# circuit.net
KiCad netlist of a schematic drawn in EAGLE
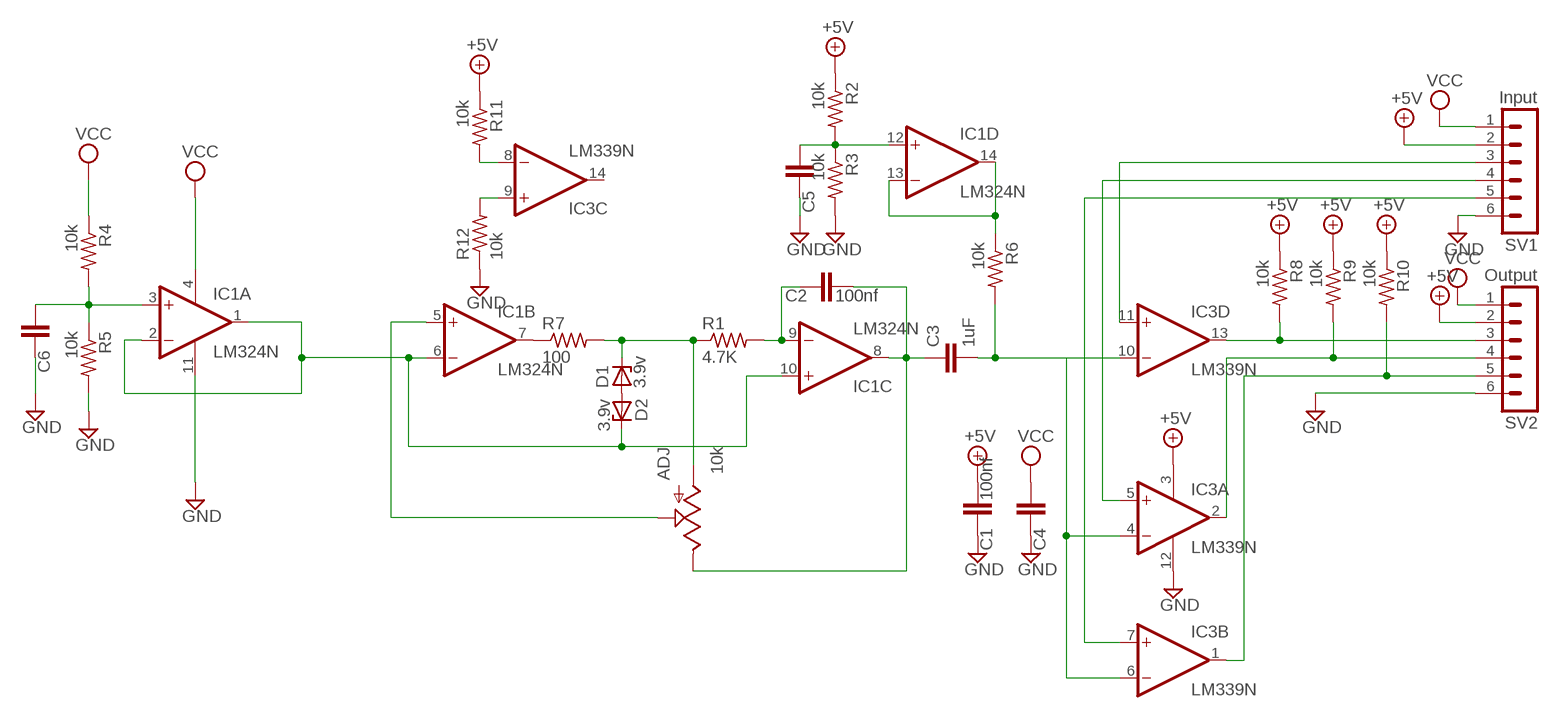
[diagram p0: schematic, sheet 1]

(export (version "E")
  (design (tool "Eeschema 10.0.6"))
  (components
    (comp (ref "ADJ")
      (value "10k")
      (footprint "eagle-import:TRIM_POT")
      (libsource (lib "eagle-import") (part "POTTRIM"))
    )
    (comp (ref "C1")
      (value "100nf")
      (footprint "eagle-import:C050-024X044")
      (libsource (lib "eagle-import") (part "C-EU050-024X044"))
    )
    (comp (ref "C2")
      (value "100nf")
      (footprint "eagle-import:C050-024X044")
      (libsource (lib "eagle-import") (part "C-EU050-024X044"))
    )
    (comp (ref "C3")
      (value "1uF")
      (footprint "eagle-import:C050-035X075")
      (libsource (lib "eagle-import") (part "resistor_C-EU050-035X075"))
    )
    (comp (ref "C4")
      (value "100nf")
      (footprint "eagle-import:C050-024X044")
      (libsource (lib "eagle-import") (part "C-EU050-024X044"))
    )
    (comp (ref "C5")
      (value "100nf")
      (footprint "eagle-import:C050-024X044")
      (libsource (lib "eagle-import") (part "C-EU050-024X044"))
    )
    (comp (ref "C6")
      (value "100nf")
      (footprint "eagle-import:C050-024X044")
      (libsource (lib "eagle-import") (part "C-EU050-024X044"))
    )
    (comp (ref "D1")
      (value "3.9v")
      (footprint "eagle-import:DO41Z10")
      (libsource (lib "eagle-import") (part "ZENER-DIODEDO41Z10"))
    )
    (comp (ref "D2")
      (value "3.9v")
      (footprint "eagle-import:DO41Z10")
      (libsource (lib "eagle-import") (part "ZENER-DIODEDO41Z10"))
    )
    (comp (ref "IC1")
      (value "LM324N")
      (footprint "eagle-import:DIL14")
      (libsource (lib "eagle-import") (part "LM324N"))
    )
    (comp (ref "IC3")
      (value "LM339N")
      (footprint "eagle-import:DIL14")
      (libsource (lib "eagle-import") (part "LM339N"))
    )
    (comp (ref "R1")
      (value "4.7K")
      (footprint "eagle-import:0207_12")
      (libsource (lib "eagle-import") (part "R-US_0207/12"))
    )
    (comp (ref "R2")
      (value "10k")
      (footprint "eagle-import:0207_10")
      (libsource (lib "eagle-import") (part "R-US_0207/10"))
    )
    (comp (ref "R3")
      (value "10k")
      (footprint "eagle-import:0207_10")
      (libsource (lib "eagle-import") (part "R-US_0207/10"))
    )
    (comp (ref "R4")
      (value "10k")
      (footprint "eagle-import:0207_10")
      (libsource (lib "eagle-import") (part "R-US_0207/10"))
    )
    (comp (ref "R5")
      (value "10k")
      (footprint "eagle-import:0207_10")
      (libsource (lib "eagle-import") (part "R-US_0207/10"))
    )
    (comp (ref "R6")
      (value "10k")
      (footprint "eagle-import:0207_10")
      (libsource (lib "eagle-import") (part "R-US_0207/10"))
    )
    (comp (ref "R7")
      (value "100")
      (footprint "eagle-import:0207_10")
      (libsource (lib "eagle-import") (part "R-US_0207/10"))
    )
    (comp (ref "R8")
      (value "10k")
      (footprint "eagle-import:0207_7")
      (libsource (lib "eagle-import") (part "R-US_0207/7"))
    )
    (comp (ref "R9")
      (value "10k")
      (footprint "eagle-import:0207_10")
      (libsource (lib "eagle-import") (part "R-US_0207/10"))
    )
    (comp (ref "R10")
      (value "10k")
      (footprint "eagle-import:0207_10")
      (libsource (lib "eagle-import") (part "R-US_0207/10"))
    )
    (comp (ref "R11")
      (value "10k")
      (footprint "eagle-import:0207_10")
      (libsource (lib "eagle-import") (part "R-US_0207/10"))
    )
    (comp (ref "R12")
      (value "10k")
      (footprint "eagle-import:0207_10")
      (libsource (lib "eagle-import") (part "R-US_0207/10"))
    )
    (comp (ref "SV1")
      (value "Input")
      (footprint "eagle-import:MA06-1")
      (libsource (lib "eagle-import") (part "MA06-1"))
    )
    (comp (ref "SV2")
      (value "Output")
      (footprint "eagle-import:MA06-1")
      (libsource (lib "eagle-import") (part "MA06-1"))
    )
  )
  (nets
    (net (code "1") (name "+5V") (class "Default")
      (node (ref "C1") (pin "2") (pinfunction "2_2") (pintype "passive"))
      (node (ref "IC3") (pin "3") (pinfunction "V+_3") (pintype "power_in"))
      (node (ref "R10") (pin "1") (pinfunction "1_1") (pintype "passive"))
      (node (ref "R11") (pin "1") (pinfunction "1_1") (pintype "passive"))
      (node (ref "R2") (pin "1") (pinfunction "1_1") (pintype "passive"))
      (node (ref "R8") (pin "1") (pinfunction "1_1") (pintype "passive"))
      (node (ref "R9") (pin "1") (pinfunction "1_1") (pintype "passive"))
      (node (ref "SV1") (pin "2") (pinfunction "2_2") (pintype "passive"))
      (node (ref "SV2") (pin "2") (pinfunction "2_2") (pintype "passive"))
    )
    (net (code "2") (name "GND") (class "Default")
      (node (ref "C1") (pin "1") (pinfunction "1_1") (pintype "passive"))
      (node (ref "C4") (pin "1") (pinfunction "1_1") (pintype "passive"))
      (node (ref "C5") (pin "1") (pinfunction "1_1") (pintype "passive"))
      (node (ref "C6") (pin "1") (pinfunction "1_1") (pintype "passive"))
      (node (ref "IC1") (pin "11") (pinfunction "V-_11") (pintype "power_in"))
      (node (ref "IC3") (pin "12") (pinfunction "GND_12") (pintype "power_in"))
      (node (ref "R12") (pin "1") (pinfunction "1_1") (pintype "passive"))
      (node (ref "R3") (pin "2") (pinfunction "2_2") (pintype "passive"))
      (node (ref "R5") (pin "2") (pinfunction "2_2") (pintype "passive"))
      (node (ref "SV1") (pin "6") (pinfunction "6_6") (pintype "passive"))
      (node (ref "SV2") (pin "6") (pinfunction "6_6") (pintype "passive"))
    )
    (net (code "3") (name "Net-(ADJ-A)") (class "Default")
      (node (ref "ADJ") (pin "3") (pinfunction "A_3") (pintype "passive"))
      (node (ref "D1") (pin "C") (pinfunction "C_C") (pintype "passive"))
      (node (ref "R1") (pin "1") (pinfunction "1_1") (pintype "passive"))
      (node (ref "R7") (pin "2") (pinfunction "2_2") (pintype "passive"))
    )
    (net (code "4") (name "Net-(ADJ-E)") (class "Default")
      (node (ref "ADJ") (pin "2") (pinfunction "E_2") (pintype "passive"))
      (node (ref "C2") (pin "2") (pinfunction "2_2") (pintype "passive"))
      (node (ref "C3") (pin "1") (pinfunction "1_1") (pintype "passive"))
      (node (ref "IC1") (pin "8") (pinfunction "OUT_8") (pintype "output"))
    )
    (net (code "5") (name "Net-(ADJ-S)") (class "Default")
      (node (ref "ADJ") (pin "1") (pinfunction "S_1") (pintype "passive"))
      (node (ref "IC1") (pin "5") (pinfunction "+IN_5") (pintype "input"))
    )
    (net (code "6") (name "Net-(D1-PadA)") (class "Default")
      (node (ref "D1") (pin "A") (pinfunction "A_A") (pintype "passive"))
      (node (ref "D2") (pin "A") (pinfunction "A_A") (pintype "passive"))
    )
    (net (code "7") (name "Net-(IC1A-+IN)") (class "Default")
      (node (ref "C6") (pin "2") (pinfunction "2_2") (pintype "passive"))
      (node (ref "IC1") (pin "3") (pinfunction "+IN_3") (pintype "input"))
      (node (ref "R4") (pin "2") (pinfunction "2_2") (pintype "passive"))
      (node (ref "R5") (pin "1") (pinfunction "1_1") (pintype "passive"))
    )
    (net (code "8") (name "Net-(IC1A--IN)") (class "Default")
      (node (ref "D2") (pin "C") (pinfunction "C_C") (pintype "passive"))
      (node (ref "IC1") (pin "1") (pinfunction "OUT_1") (pintype "output"))
      (node (ref "IC1") (pin "10") (pinfunction "+IN_10") (pintype "input"))
      (node (ref "IC1") (pin "2") (pinfunction "-IN_2") (pintype "input"))
      (node (ref "IC1") (pin "6") (pinfunction "-IN_6") (pintype "input"))
    )
    (net (code "9") (name "Net-(IC1B-OUT)") (class "Default")
      (node (ref "IC1") (pin "7") (pinfunction "OUT_7") (pintype "output"))
      (node (ref "R7") (pin "1") (pinfunction "1_1") (pintype "passive"))
    )
    (net (code "10") (name "Net-(IC1C--IN)") (class "Default")
      (node (ref "C2") (pin "1") (pinfunction "1_1") (pintype "passive"))
      (node (ref "IC1") (pin "9") (pinfunction "-IN_9") (pintype "input"))
      (node (ref "R1") (pin "2") (pinfunction "2_2") (pintype "passive"))
    )
    (net (code "11") (name "Net-(IC1D-+IN)") (class "Default")
      (node (ref "C5") (pin "2") (pinfunction "2_2") (pintype "passive"))
      (node (ref "IC1") (pin "12") (pinfunction "+IN_12") (pintype "input"))
      (node (ref "R2") (pin "2") (pinfunction "2_2") (pintype "passive"))
      (node (ref "R3") (pin "1") (pinfunction "1_1") (pintype "passive"))
    )
    (net (code "12") (name "Net-(IC1D--IN)") (class "Default")
      (node (ref "IC1") (pin "13") (pinfunction "-IN_13") (pintype "input"))
      (node (ref "IC1") (pin "14") (pinfunction "OUT_14") (pintype "output"))
      (node (ref "R6") (pin "1") (pinfunction "1_1") (pintype "passive"))
    )
    (net (code "13") (name "Net-(IC3A-+IN)") (class "Default")
      (node (ref "IC3") (pin "5") (pinfunction "+IN_5") (pintype "input"))
      (node (ref "SV1") (pin "4") (pinfunction "4_4") (pintype "passive"))
    )
    (net (code "14") (name "Net-(IC3A--IN)") (class "Default")
      (node (ref "C3") (pin "2") (pinfunction "2_2") (pintype "passive"))
      (node (ref "IC3") (pin "10") (pinfunction "-IN_10") (pintype "input"))
      (node (ref "IC3") (pin "4") (pinfunction "-IN_4") (pintype "input"))
      (node (ref "IC3") (pin "6") (pinfunction "-IN_6") (pintype "input"))
      (node (ref "R6") (pin "2") (pinfunction "2_2") (pintype "passive"))
    )
    (net (code "15") (name "Net-(IC3A-OUT)") (class "Default")
      (node (ref "IC3") (pin "2") (pinfunction "OUT_2") (pintype "open_collector"))
      (node (ref "R9") (pin "2") (pinfunction "2_2") (pintype "passive"))
      (node (ref "SV2") (pin "4") (pinfunction "4_4") (pintype "passive"))
    )
    (net (code "16") (name "Net-(IC3B-+IN)") (class "Default")
      (node (ref "IC3") (pin "7") (pinfunction "+IN_7") (pintype "input"))
      (node (ref "SV1") (pin "5") (pinfunction "5_5") (pintype "passive"))
    )
    (net (code "17") (name "Net-(IC3B-OUT)") (class "Default")
      (node (ref "IC3") (pin "1") (pinfunction "OUT_1") (pintype "open_collector"))
      (node (ref "R10") (pin "2") (pinfunction "2_2") (pintype "passive"))
      (node (ref "SV2") (pin "5") (pinfunction "5_5") (pintype "passive"))
    )
    (net (code "18") (name "Net-(IC3C-+IN)") (class "Default")
      (node (ref "IC3") (pin "9") (pinfunction "+IN_9") (pintype "input"))
      (node (ref "R12") (pin "2") (pinfunction "2_2") (pintype "passive"))
    )
    (net (code "19") (name "Net-(IC3C--IN)") (class "Default")
      (node (ref "IC3") (pin "8") (pinfunction "-IN_8") (pintype "input"))
      (node (ref "R11") (pin "2") (pinfunction "2_2") (pintype "passive"))
    )
    (net (code "20") (name "Net-(IC3D-+IN)") (class "Default")
      (node (ref "IC3") (pin "11") (pinfunction "+IN_11") (pintype "input"))
      (node (ref "SV1") (pin "3") (pinfunction "3_3") (pintype "passive"))
    )
    (net (code "21") (name "Net-(IC3D-OUT)") (class "Default")
      (node (ref "IC3") (pin "13") (pinfunction "OUT_13") (pintype "open_collector"))
      (node (ref "R8") (pin "2") (pinfunction "2_2") (pintype "passive"))
      (node (ref "SV2") (pin "3") (pinfunction "3_3") (pintype "passive"))
    )
    (net (code "22") (name "VCC") (class "Default")
      (node (ref "C4") (pin "2") (pinfunction "2_2") (pintype "passive"))
      (node (ref "IC1") (pin "4") (pinfunction "V+_4") (pintype "power_in"))
      (node (ref "R4") (pin "1") (pinfunction "1_1") (pintype "passive"))
      (node (ref "SV1") (pin "1") (pinfunction "1_1") (pintype "passive"))
      (node (ref "SV2") (pin "1") (pinfunction "1_1") (pintype "passive"))
    )
    (net (code "23") (name "unconnected-(IC3C-OUT-Pad14)") (class "Default")
      (node (ref "IC3") (pin "14") (pinfunction "OUT_14") (pintype "open_collector"))
    )
  )
)
